# Pulsera_con_GND.net
KiCad netlist of a schematic drawn in EasyEDA
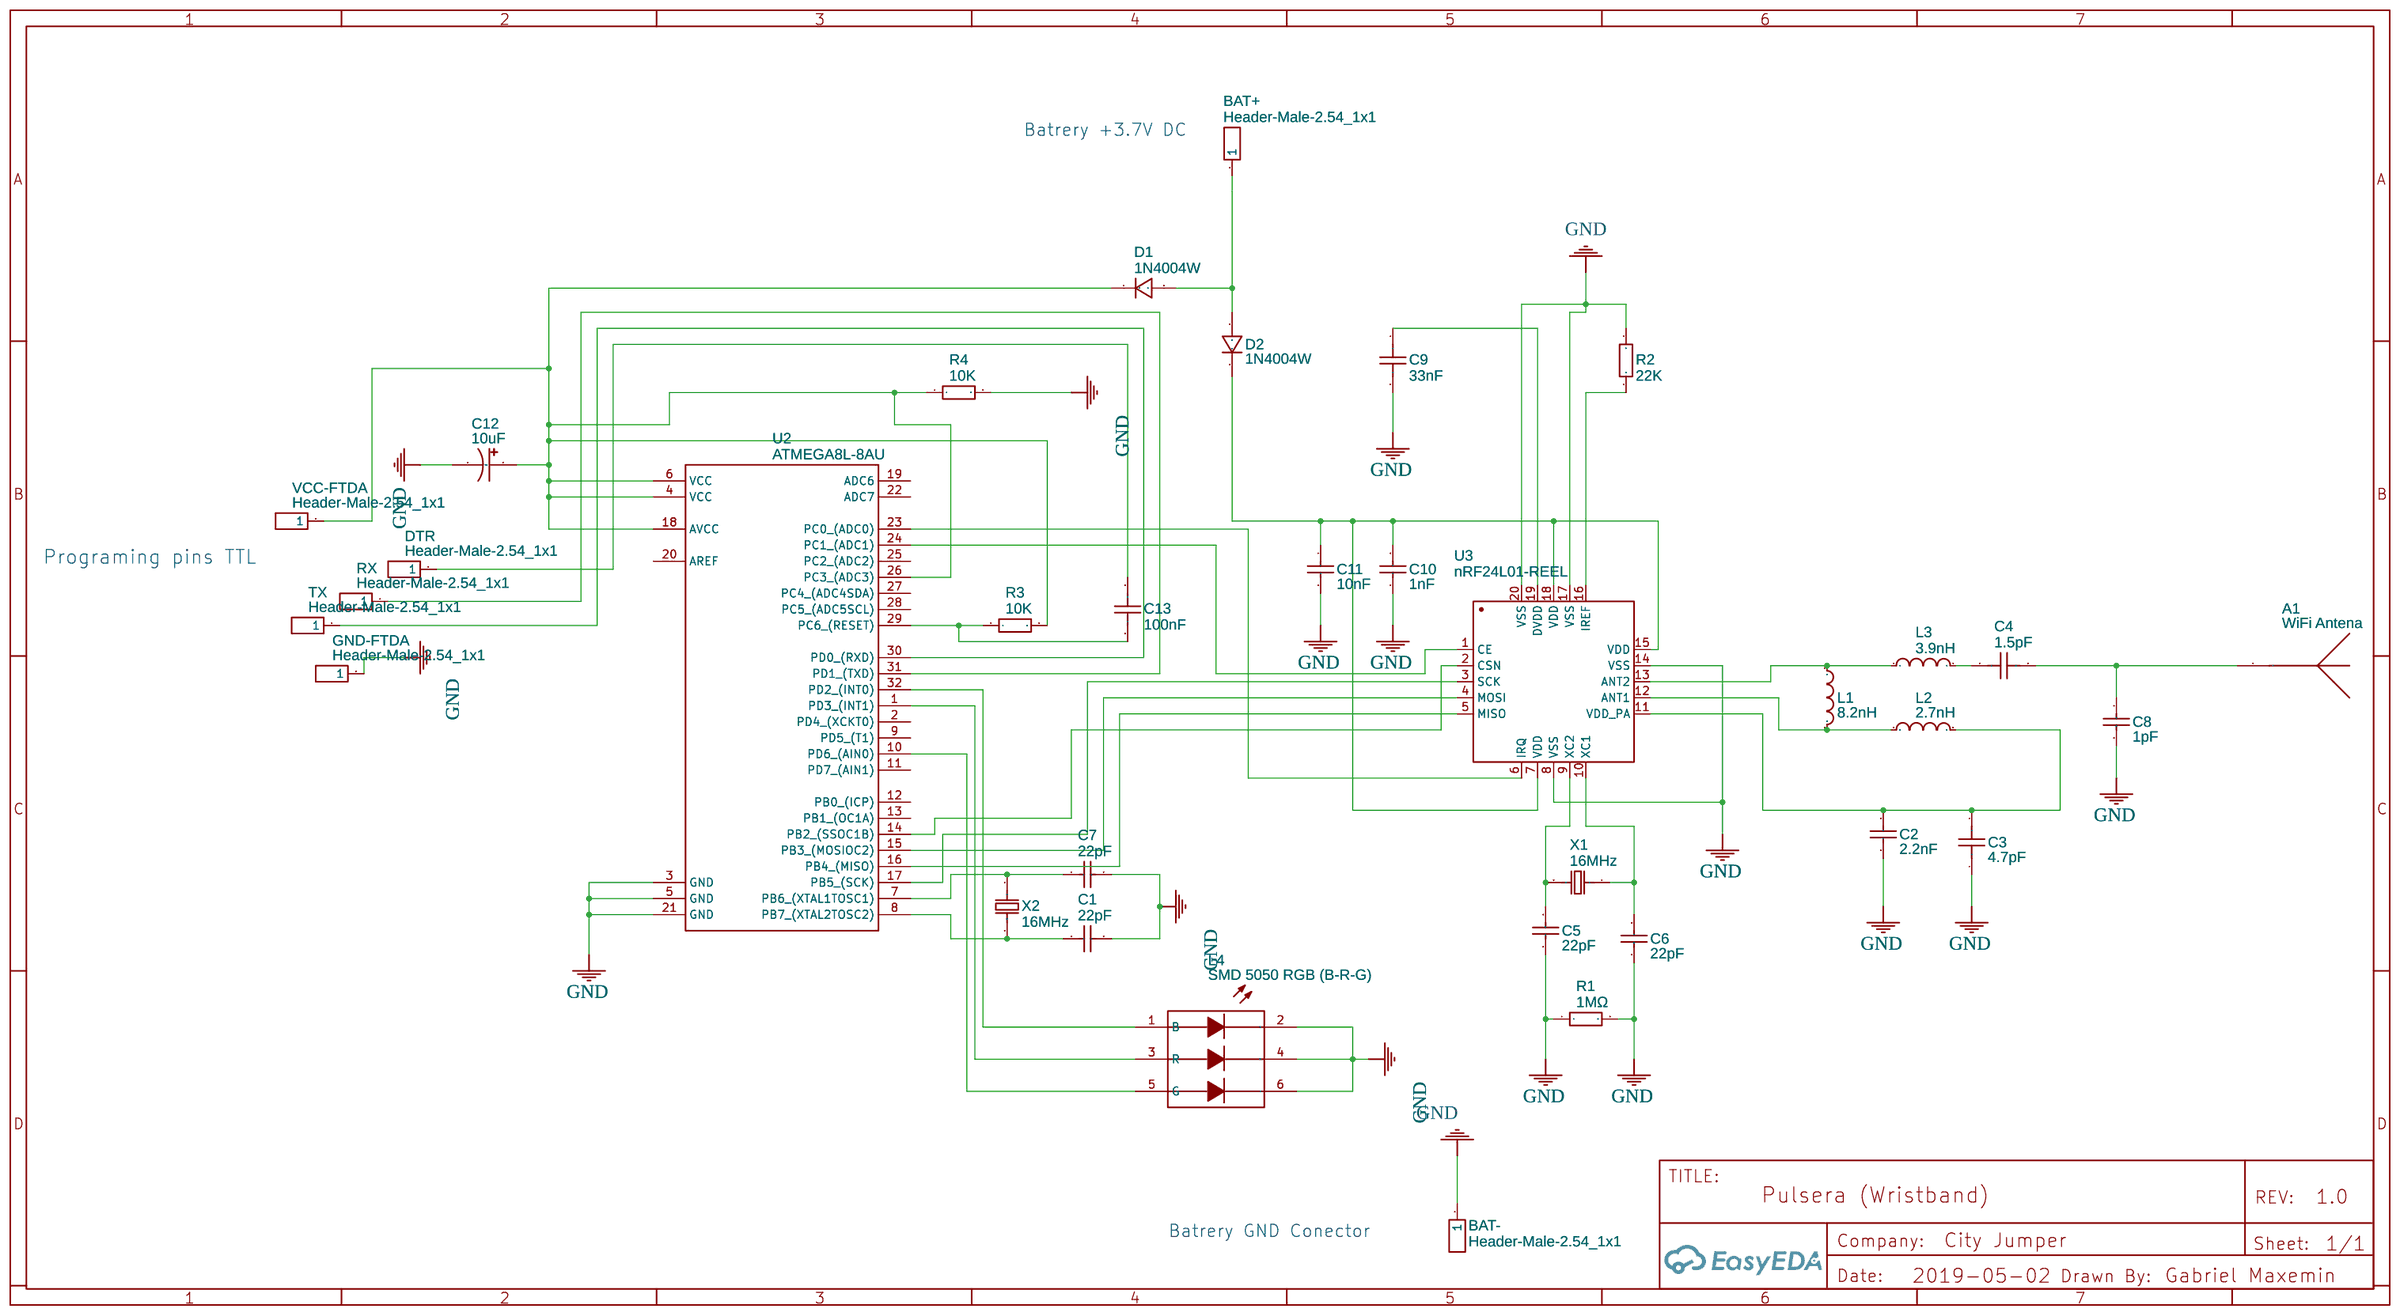
[diagram p0: schematic sheet]

(export (version "E")
  (design (tool "Eeschema 10.0.6"))
  (components
    (comp (ref "A1")
      (value "WiFi Antena")
      (fields (field (name "BOM_Manufacturer Part") "New SchematicLib"))
      (libsource (lib "") (part "Unknown_1430_305"))
    )
    (comp (ref "BAT+")
      (value "Header-Male-2.54_1x1")
      (fields (field (name "BOM_Supplier Part") "C81276"))
      (libsource (lib "") (part "Unknown_760_-15"))
    )
    (comp (ref "BAT-")
      (value "Header-Male-2.54_1x1")
      (fields (field (name "BOM_Supplier Part") "C81276"))
      (libsource (lib "") (part "Unknown_900_655"))
    )
    (comp (ref "C1")
      (value "22pF")
      (fields
        (field (name "BOM_Manufacturer Part") "0402CG220J500NT")
        (field (name "BOM_Supplier Part") "C1555")
      )
      (libsource (lib "") (part "0402CG220J500NT"))
    )
    (comp (ref "C2")
      (value "2.2nF")
      (fields
        (field (name "BOM_Manufacturer Part") "0402B222K500NT")
        (field (name "BOM_Supplier Part") "C1531")
      )
      (libsource (lib "") (part "0402B222K500NT"))
    )
    (comp (ref "C3")
      (value "4.7pF")
      (fields
        (field (name "BOM_Manufacturer Part") "GJM1555C1H4R7CB01D")
        (field (name "BOM_Supplier Part") "C85883")
      )
      (libsource (lib "") (part "GJM1555C1H4R7CB01D"))
    )
    (comp (ref "C4")
      (value "1.5pF")
      (fields
        (field (name "BOM_Manufacturer Part") "GJM1555C1H1R5BB01D")
        (field (name "BOM_Supplier Part") "C76900")
      )
      (libsource (lib "") (part "GJM1555C1H1R5BB01D"))
    )
    (comp (ref "C5")
      (value "22pF")
      (fields
        (field (name "BOM_Manufacturer Part") "0402CG220J500NT")
        (field (name "BOM_Supplier Part") "C1555")
      )
      (libsource (lib "") (part "0402CG220J500NT_1"))
    )
    (comp (ref "C6")
      (value "22pF")
      (fields
        (field (name "BOM_Manufacturer Part") "0402CG220J500NT")
        (field (name "BOM_Supplier Part") "C1555")
      )
      (libsource (lib "") (part "0402CG220J500NT_1"))
    )
    (comp (ref "C7")
      (value "22pF")
      (fields
        (field (name "BOM_Manufacturer Part") "0402CG220J500NT")
        (field (name "BOM_Supplier Part") "C1555")
      )
      (libsource (lib "") (part "0402CG220J500NT"))
    )
    (comp (ref "C8")
      (value "1pF")
      (fields
        (field (name "BOM_Manufacturer Part") "GJM1555C1H1R0BB01D")
        (field (name "BOM_Supplier Part") "C76898")
      )
      (libsource (lib "") (part "GJM1555C1H1R0BB01D"))
    )
    (comp (ref "C9")
      (value "33nF")
      (fields
        (field (name "BOM_Manufacturer Part") "GRM155R71E333KA88D")
        (field (name "BOM_Supplier Part") "C77016")
      )
      (libsource (lib "") (part "GRM155R71E333KA88D"))
    )
    (comp (ref "C10")
      (value "1nF")
      (fields
        (field (name "BOM_Manufacturer Part") "CL05B102KB5NNNC")
        (field (name "BOM_Supplier Part") "C14442")
      )
      (libsource (lib "") (part "CL05B102KB5NNNC"))
    )
    (comp (ref "C11")
      (value "10nF")
      (fields
        (field (name "BOM_Manufacturer Part") "GRM155R71H103KA88D")
        (field (name "BOM_Supplier Part") "C77019")
      )
      (libsource (lib "") (part "GRM155R71H103KA88D"))
    )
    (comp (ref "C12")
      (value "10uF")
      (fields
        (field (name "BOM_Manufacturer Part") "EEE1EA100WR")
        (field (name "BOM_Supplier Part") "C178501")
      )
      (libsource (lib "") (part "EEE1EA100WR"))
    )
    (comp (ref "C13")
      (value "100nF")
      (fields
        (field (name "BOM_Manufacturer Part") "GRM155R61C104KA88D")
        (field (name "BOM_Supplier Part") "C77005")
      )
      (libsource (lib "") (part "GRM155R61C104KA88D"))
    )
    (comp (ref "D1")
      (value "1N4004W")
      (fields (field (name "BOM_Supplier Part") "C162734"))
      (libsource (lib "") (part "Unknown_705_70"))
    )
    (comp (ref "D2")
      (value "1N4004W")
      (fields (field (name "BOM_Supplier Part") "C162734"))
      (libsource (lib "") (part "Unknown_760_105"))
    )
    (comp (ref "DTR")
      (value "Header-Male-2.54_1x1")
      (fields (field (name "BOM_Supplier Part") "C81276"))
      (libsource (lib "") (part "Unknown_250_245"))
    )
    (comp (ref "GND-FTDA")
      (value "Header-Male-2.54_1x1")
      (fields (field (name "BOM_Supplier Part") "C81276"))
      (libsource (lib "") (part "Unknown_205_310"))
    )
    (comp (ref "L1")
      (value "8.2nH")
      (fields
        (field (name "BOM_Manufacturer Part") "SDCL1005C8N2JTDF")
        (field (name "BOM_Supplier Part") "C16208")
      )
      (libsource (lib "") (part "SDCL1005C8N2JTDF"))
    )
    (comp (ref "L2")
      (value "2.7nH")
      (fields
        (field (name "BOM_Manufacturer Part") "SDCL1005C2N7STDF")
        (field (name "BOM_Supplier Part") "C27123")
      )
      (libsource (lib "") (part "SDCL1005C2N7STDF"))
    )
    (comp (ref "L3")
      (value "3.9nH")
      (fields
        (field (name "BOM_Manufacturer Part") "SDCL1005C3N9STDF")
        (field (name "BOM_Supplier Part") "C14033")
      )
      (libsource (lib "") (part "SDCL1005C3N9STDF"))
    )
    (comp (ref "L4")
      (value "SMD 5050 RGB (B-R-G)")
      (fields (field (name "BOM_Manufacturer Part") "SMD 5050 RGB"))
      (libsource (lib "") (part "Unknown_740_520"))
    )
    (comp (ref "R1")
      (value "1MΩ")
      (fields
        (field (name "BOM_Manufacturer Part") "RC0402FR-071ML")
        (field (name "BOM_Supplier Part") "603-RC0402FR-071ML")
      )
      (libsource (lib "") (part "Unknown_980_525"))
    )
    (comp (ref "R2")
      (value "22K")
      (fields
        (field (name "BOM_Manufacturer Part") "0402WGJ0223TCE")
        (field (name "BOM_Supplier Part") "C25547")
      )
      (libsource (lib "") (part "0402WGJ0223TCE"))
    )
    (comp (ref "R3")
      (value "10K")
      (fields
        (field (name "BOM_Manufacturer Part") "0402WGJ0103TCE")
        (field (name "BOM_Supplier Part") "C25531")
      )
      (libsource (lib "") (part "0402WGJ0103TCE"))
    )
    (comp (ref "R4")
      (value "10K")
      (fields
        (field (name "BOM_Manufacturer Part") "0402WGJ0103TCE")
        (field (name "BOM_Supplier Part") "C25531")
      )
      (libsource (lib "") (part "0402WGJ0103TCE"))
    )
    (comp (ref "RX")
      (value "Header-Male-2.54_1x1")
      (fields (field (name "BOM_Supplier Part") "C81276"))
      (libsource (lib "") (part "Unknown_220_265"))
    )
    (comp (ref "TX")
      (value "Header-Male-2.54_1x1")
      (fields (field (name "BOM_Supplier Part") "C81276"))
      (libsource (lib "") (part "Unknown_190_280"))
    )
    (comp (ref "U2")
      (value "ATMEGA8L-8AU")
      (fields (field (name "BOM_Supplier Part") "C9755"))
      (libsource (lib "") (part "Unknown_480_325"))
    )
    (comp (ref "U3")
      (value "nRF24L01-REEL")
      (fields (field (name "BOM_Supplier Part") "C93664"))
      (libsource (lib "") (part "Unknown_960_315"))
    )
    (comp (ref "VCC-FTDA")
      (value "Header-Male-2.54_1x1")
      (fields (field (name "BOM_Supplier Part") "C81276"))
      (libsource (lib "") (part "Unknown_180_215"))
    )
    (comp (ref "X1")
      (value "16MHz")
      (fields
        (field (name "BOM_Manufacturer Part") "X49SSM16MSD2SI")
        (field (name "BOM_Supplier Part") "C96138")
      )
      (libsource (lib "") (part "X49SSM16MSD2SI_1"))
    )
    (comp (ref "X2")
      (value "16MHz")
      (fields
        (field (name "BOM_Manufacturer Part") "X49SSM16MSD2SI")
        (field (name "BOM_Supplier Part") "C96138")
      )
      (libsource (lib "") (part "X49SSM16MSD2SI"))
    )
  )
  (nets
    (net (code "1") (name "GND") (class "Default")
      (node (ref "BAT-") (pin "1") (pinfunction "1_1") (pintype "input"))
      (node (ref "C1") (pin "2") (pinfunction "2_2") (pintype "input"))
      (node (ref "C10") (pin "1") (pinfunction "1_1") (pintype "input"))
      (node (ref "C11") (pin "2") (pinfunction "2_2") (pintype "input"))
      (node (ref "C12") (pin "2") (pinfunction "2_2") (pintype "unspecified"))
      (node (ref "C2") (pin "1") (pinfunction "1_1") (pintype "input"))
      (node (ref "C3") (pin "1") (pinfunction "1_1") (pintype "unspecified"))
      (node (ref "C5") (pin "1") (pinfunction "1_1") (pintype "input"))
      (node (ref "C6") (pin "1") (pinfunction "1_1") (pintype "input"))
      (node (ref "C7") (pin "2") (pinfunction "2_2") (pintype "input"))
      (node (ref "C8") (pin "2") (pinfunction "2_2") (pintype "input"))
      (node (ref "C9") (pin "2") (pinfunction "2_2") (pintype "unspecified"))
      (node (ref "GND-FTDA") (pin "1") (pinfunction "1_1") (pintype "input"))
      (node (ref "L4") (pin "2") (pinfunction "B-_2") (pintype "unspecified"))
      (node (ref "L4") (pin "4") (pinfunction "R-_4") (pintype "unspecified"))
      (node (ref "L4") (pin "6") (pinfunction "-g_6") (pintype "unspecified"))
      (node (ref "R1") (pin "1") (pinfunction "1_1") (pintype "input"))
      (node (ref "R1") (pin "2") (pinfunction "2_2") (pintype "input"))
      (node (ref "R2") (pin "2") (pinfunction "2_2") (pintype "input"))
      (node (ref "R4") (pin "2") (pinfunction "2_2") (pintype "input"))
      (node (ref "U2") (pin "21") (pinfunction "GND_21") (pintype "passive"))
      (node (ref "U2") (pin "3") (pinfunction "GND_3") (pintype "passive"))
      (node (ref "U2") (pin "5") (pinfunction "GND_5") (pintype "passive"))
      (node (ref "U3") (pin "14") (pinfunction "VSS_14") (pintype "unspecified"))
      (node (ref "U3") (pin "17") (pinfunction "VSS_17") (pintype "unspecified"))
      (node (ref "U3") (pin "20") (pinfunction "VSS_20") (pintype "unspecified"))
      (node (ref "U3") (pin "8") (pinfunction "VSS_8") (pintype "unspecified"))
    )
    (net (code "2") (name "Net-(A1-Pad1)") (class "Default")
      (node (ref "A1") (pin "1") (pinfunction "1_1") (pintype "output"))
      (node (ref "C4") (pin "2") (pinfunction "2_2") (pintype "unspecified"))
      (node (ref "C8") (pin "1") (pinfunction "1_1") (pintype "input"))
    )
    (net (code "3") (name "Net-(BAT+-Pad1)") (class "Default")
      (node (ref "BAT+") (pin "1") (pinfunction "1_1") (pintype "input"))
      (node (ref "D1") (pin "2") (pinfunction "2_2") (pintype "unspecified"))
      (node (ref "D2") (pin "2") (pinfunction "2_2") (pintype "unspecified"))
    )
    (net (code "4") (name "Net-(C4-Pad1)") (class "Default")
      (node (ref "C4") (pin "1") (pinfunction "1_1") (pintype "unspecified"))
      (node (ref "L3") (pin "2") (pinfunction "2_2") (pintype "unspecified"))
    )
    (net (code "5") (name "Net-(C10-Pad2)") (class "Default")
      (node (ref "C10") (pin "2") (pinfunction "2_2") (pintype "input"))
      (node (ref "C11") (pin "1") (pinfunction "1_1") (pintype "input"))
      (node (ref "D2") (pin "1") (pinfunction "1_1") (pintype "unspecified"))
      (node (ref "U3") (pin "15") (pinfunction "VDD_15") (pintype "unspecified"))
      (node (ref "U3") (pin "18") (pinfunction "VDD_18") (pintype "unspecified"))
      (node (ref "U3") (pin "7") (pinfunction "VDD_7") (pintype "unspecified"))
    )
    (net (code "6") (name "Net-(C13-Pad2)") (class "Default")
      (node (ref "C13") (pin "2") (pinfunction "2_2") (pintype "unspecified"))
      (node (ref "DTR") (pin "1") (pinfunction "1_1") (pintype "input"))
    )
    (net (code "7") (name "Net-(L4-B)") (class "Default")
      (node (ref "L4") (pin "1") (pinfunction "B_1") (pintype "unspecified"))
      (node (ref "U2") (pin "32") (pinfunction "PD2_(INT0)_32") (pintype "bidirectional"))
    )
    (net (code "8") (name "Net-(L4-G)") (class "Default")
      (node (ref "L4") (pin "5") (pinfunction "G_5") (pintype "unspecified"))
      (node (ref "U2") (pin "10") (pinfunction "PD6_(AIN0)_10") (pintype "bidirectional"))
    )
    (net (code "9") (name "Net-(L4-R)") (class "Default")
      (node (ref "L4") (pin "3") (pinfunction "R_3") (pintype "unspecified"))
      (node (ref "U2") (pin "1") (pinfunction "PD3_(INT1)_1") (pintype "bidirectional"))
    )
    (net (code "10") (name "Net-(U2-AVCC)") (class "Default")
      (node (ref "C12") (pin "1") (pinfunction "1_1") (pintype "unspecified"))
      (node (ref "D1") (pin "1") (pinfunction "1_1") (pintype "unspecified"))
      (node (ref "R3") (pin "2") (pinfunction "2_2") (pintype "input"))
      (node (ref "R4") (pin "1") (pinfunction "1_1") (pintype "input"))
      (node (ref "U2") (pin "18") (pinfunction "AVCC_18") (pintype "passive"))
      (node (ref "U2") (pin "26") (pinfunction "PC3_(ADC3)_26") (pintype "bidirectional"))
      (node (ref "U2") (pin "4") (pinfunction "VCC_4") (pintype "passive"))
      (node (ref "U2") (pin "6") (pinfunction "VCC_6") (pintype "passive"))
      (node (ref "VCC-FTDA") (pin "1") (pinfunction "1_1") (pintype "input"))
    )
    (net (code "11") (name "Net-(U2-PB2_(SSOC1B))") (class "Default")
      (node (ref "U2") (pin "14") (pinfunction "PB2_(SSOC1B)_14") (pintype "bidirectional"))
      (node (ref "U3") (pin "2") (pinfunction "CSN_2") (pintype "unspecified"))
    )
    (net (code "12") (name "Net-(U2-PB3_(MOSIOC2))") (class "Default")
      (node (ref "U2") (pin "15") (pinfunction "PB3_(MOSIOC2)_15") (pintype "bidirectional"))
      (node (ref "U3") (pin "4") (pinfunction "MOSI_4") (pintype "unspecified"))
    )
    (net (code "13") (name "Net-(U2-PB4_(MISO))") (class "Default")
      (node (ref "U2") (pin "16") (pinfunction "PB4_(MISO)_16") (pintype "bidirectional"))
      (node (ref "U3") (pin "5") (pinfunction "MISO_5") (pintype "unspecified"))
    )
    (net (code "14") (name "Net-(U2-PB5_(SCK))") (class "Default")
      (node (ref "U2") (pin "17") (pinfunction "PB5_(SCK)_17") (pintype "bidirectional"))
      (node (ref "U3") (pin "3") (pinfunction "SCK_3") (pintype "unspecified"))
    )
    (net (code "15") (name "Net-(U2-PB6_(XTAL1TOSC1))") (class "Default")
      (node (ref "C7") (pin "1") (pinfunction "1_1") (pintype "input"))
      (node (ref "U2") (pin "7") (pinfunction "PB6_(XTAL1TOSC1)_7") (pintype "bidirectional"))
      (node (ref "X2") (pin "1") (pinfunction "1_1") (pintype "unspecified"))
    )
    (net (code "16") (name "Net-(U2-PB7_(XTAL2TOSC2))") (class "Default")
      (node (ref "C1") (pin "1") (pinfunction "1_1") (pintype "input"))
      (node (ref "U2") (pin "8") (pinfunction "PB7_(XTAL2TOSC2)_8") (pintype "bidirectional"))
      (node (ref "X2") (pin "2") (pinfunction "2_2") (pintype "unspecified"))
    )
    (net (code "17") (name "Net-(U2-PC0_(ADC0))") (class "Default")
      (node (ref "U2") (pin "23") (pinfunction "PC0_(ADC0)_23") (pintype "bidirectional"))
      (node (ref "U3") (pin "6") (pinfunction "IRQ_6") (pintype "unspecified"))
    )
    (net (code "18") (name "Net-(U2-PC1_(ADC1))") (class "Default")
      (node (ref "U2") (pin "24") (pinfunction "PC1_(ADC1)_24") (pintype "bidirectional"))
      (node (ref "U3") (pin "1") (pinfunction "CE_1") (pintype "unspecified"))
    )
    (net (code "19") (name "Net-(U2-PC6_(RESET))") (class "Default")
      (node (ref "C13") (pin "1") (pinfunction "1_1") (pintype "unspecified"))
      (node (ref "R3") (pin "1") (pinfunction "1_1") (pintype "input"))
      (node (ref "U2") (pin "29") (pinfunction "PC6_(RESET)_29") (pintype "bidirectional"))
    )
    (net (code "20") (name "Net-(U2-PD0_(RXD))") (class "Default")
      (node (ref "TX") (pin "1") (pinfunction "1_1") (pintype "input"))
      (node (ref "U2") (pin "30") (pinfunction "PD0_(RXD)_30") (pintype "bidirectional"))
    )
    (net (code "21") (name "Net-(U2-PD1_(TXD))") (class "Default")
      (node (ref "RX") (pin "1") (pinfunction "1_1") (pintype "input"))
      (node (ref "U2") (pin "31") (pinfunction "PD1_(TXD)_31") (pintype "bidirectional"))
    )
    (net (code "22") (name "Net-(U3-ANT1)") (class "Default")
      (node (ref "L1") (pin "2") (pinfunction "2_2") (pintype "unspecified"))
      (node (ref "L2") (pin "1") (pinfunction "1_1") (pintype "unspecified"))
      (node (ref "U3") (pin "12") (pinfunction "ANT1_12") (pintype "unspecified"))
    )
    (net (code "23") (name "Net-(U3-ANT2)") (class "Default")
      (node (ref "L1") (pin "1") (pinfunction "1_1") (pintype "unspecified"))
      (node (ref "L3") (pin "1") (pinfunction "1_1") (pintype "unspecified"))
      (node (ref "U3") (pin "13") (pinfunction "ANT2_13") (pintype "unspecified"))
    )
    (net (code "24") (name "Net-(U3-DVDD)") (class "Default")
      (node (ref "C9") (pin "1") (pinfunction "1_1") (pintype "unspecified"))
      (node (ref "U3") (pin "19") (pinfunction "DVDD_19") (pintype "unspecified"))
    )
    (net (code "25") (name "Net-(U3-IREF)") (class "Default")
      (node (ref "R2") (pin "1") (pinfunction "1_1") (pintype "input"))
      (node (ref "U3") (pin "16") (pinfunction "IREF_16") (pintype "unspecified"))
    )
    (net (code "26") (name "Net-(U3-VDD_PA)") (class "Default")
      (node (ref "C2") (pin "2") (pinfunction "2_2") (pintype "input"))
      (node (ref "C3") (pin "2") (pinfunction "2_2") (pintype "unspecified"))
      (node (ref "L2") (pin "2") (pinfunction "2_2") (pintype "unspecified"))
      (node (ref "U3") (pin "11") (pinfunction "VDD_PA_11") (pintype "unspecified"))
    )
    (net (code "27") (name "Net-(U3-XC1)") (class "Default")
      (node (ref "C6") (pin "2") (pinfunction "2_2") (pintype "input"))
      (node (ref "U3") (pin "10") (pinfunction "XC1_10") (pintype "unspecified"))
      (node (ref "X1") (pin "1") (pinfunction "1_1") (pintype "unspecified"))
    )
    (net (code "28") (name "Net-(U3-XC2)") (class "Default")
      (node (ref "C5") (pin "2") (pinfunction "2_2") (pintype "input"))
      (node (ref "U3") (pin "9") (pinfunction "XC2_9") (pintype "unspecified"))
      (node (ref "X1") (pin "2") (pinfunction "2_2") (pintype "unspecified"))
    )
    (net (code "29") (name "unconnected-(U2-ADC6-Pad19)") (class "Default")
      (node (ref "U2") (pin "19") (pinfunction "ADC6_19") (pintype "unspecified"))
    )
    (net (code "30") (name "unconnected-(U2-ADC7-Pad22)") (class "Default")
      (node (ref "U2") (pin "22") (pinfunction "ADC7_22") (pintype "unspecified"))
    )
    (net (code "31") (name "unconnected-(U2-AREF-Pad20)") (class "Default")
      (node (ref "U2") (pin "20") (pinfunction "AREF_20") (pintype "unspecified"))
    )
    (net (code "32") (name "unconnected-(U2-PB0_(ICP)-Pad12)") (class "Default")
      (node (ref "U2") (pin "12") (pinfunction "PB0_(ICP)_12") (pintype "bidirectional"))
    )
    (net (code "33") (name "unconnected-(U2-PB1_(OC1A)-Pad13)") (class "Default")
      (node (ref "U2") (pin "13") (pinfunction "PB1_(OC1A)_13") (pintype "bidirectional"))
    )
    (net (code "34") (name "unconnected-(U2-PC2_(ADC2)-Pad25)") (class "Default")
      (node (ref "U2") (pin "25") (pinfunction "PC2_(ADC2)_25") (pintype "bidirectional"))
    )
    (net (code "35") (name "unconnected-(U2-PC4_(ADC4SDA)-Pad27)") (class "Default")
      (node (ref "U2") (pin "27") (pinfunction "PC4_(ADC4SDA)_27") (pintype "bidirectional"))
    )
    (net (code "36") (name "unconnected-(U2-PC5_(ADC5SCL)-Pad28)") (class "Default")
      (node (ref "U2") (pin "28") (pinfunction "PC5_(ADC5SCL)_28") (pintype "bidirectional"))
    )
    (net (code "37") (name "unconnected-(U2-PD4_(XCKT0)-Pad2)") (class "Default")
      (node (ref "U2") (pin "2") (pinfunction "PD4_(XCKT0)_2") (pintype "bidirectional"))
    )
    (net (code "38") (name "unconnected-(U2-PD5_(T1)-Pad9)") (class "Default")
      (node (ref "U2") (pin "9") (pinfunction "PD5_(T1)_9") (pintype "bidirectional"))
    )
    (net (code "39") (name "unconnected-(U2-PD7_(AIN1)-Pad11)") (class "Default")
      (node (ref "U2") (pin "11") (pinfunction "PD7_(AIN1)_11") (pintype "bidirectional"))
    )
  )
)
